# BeanShield.net
KiCad netlist of a schematic drawn in EAGLE
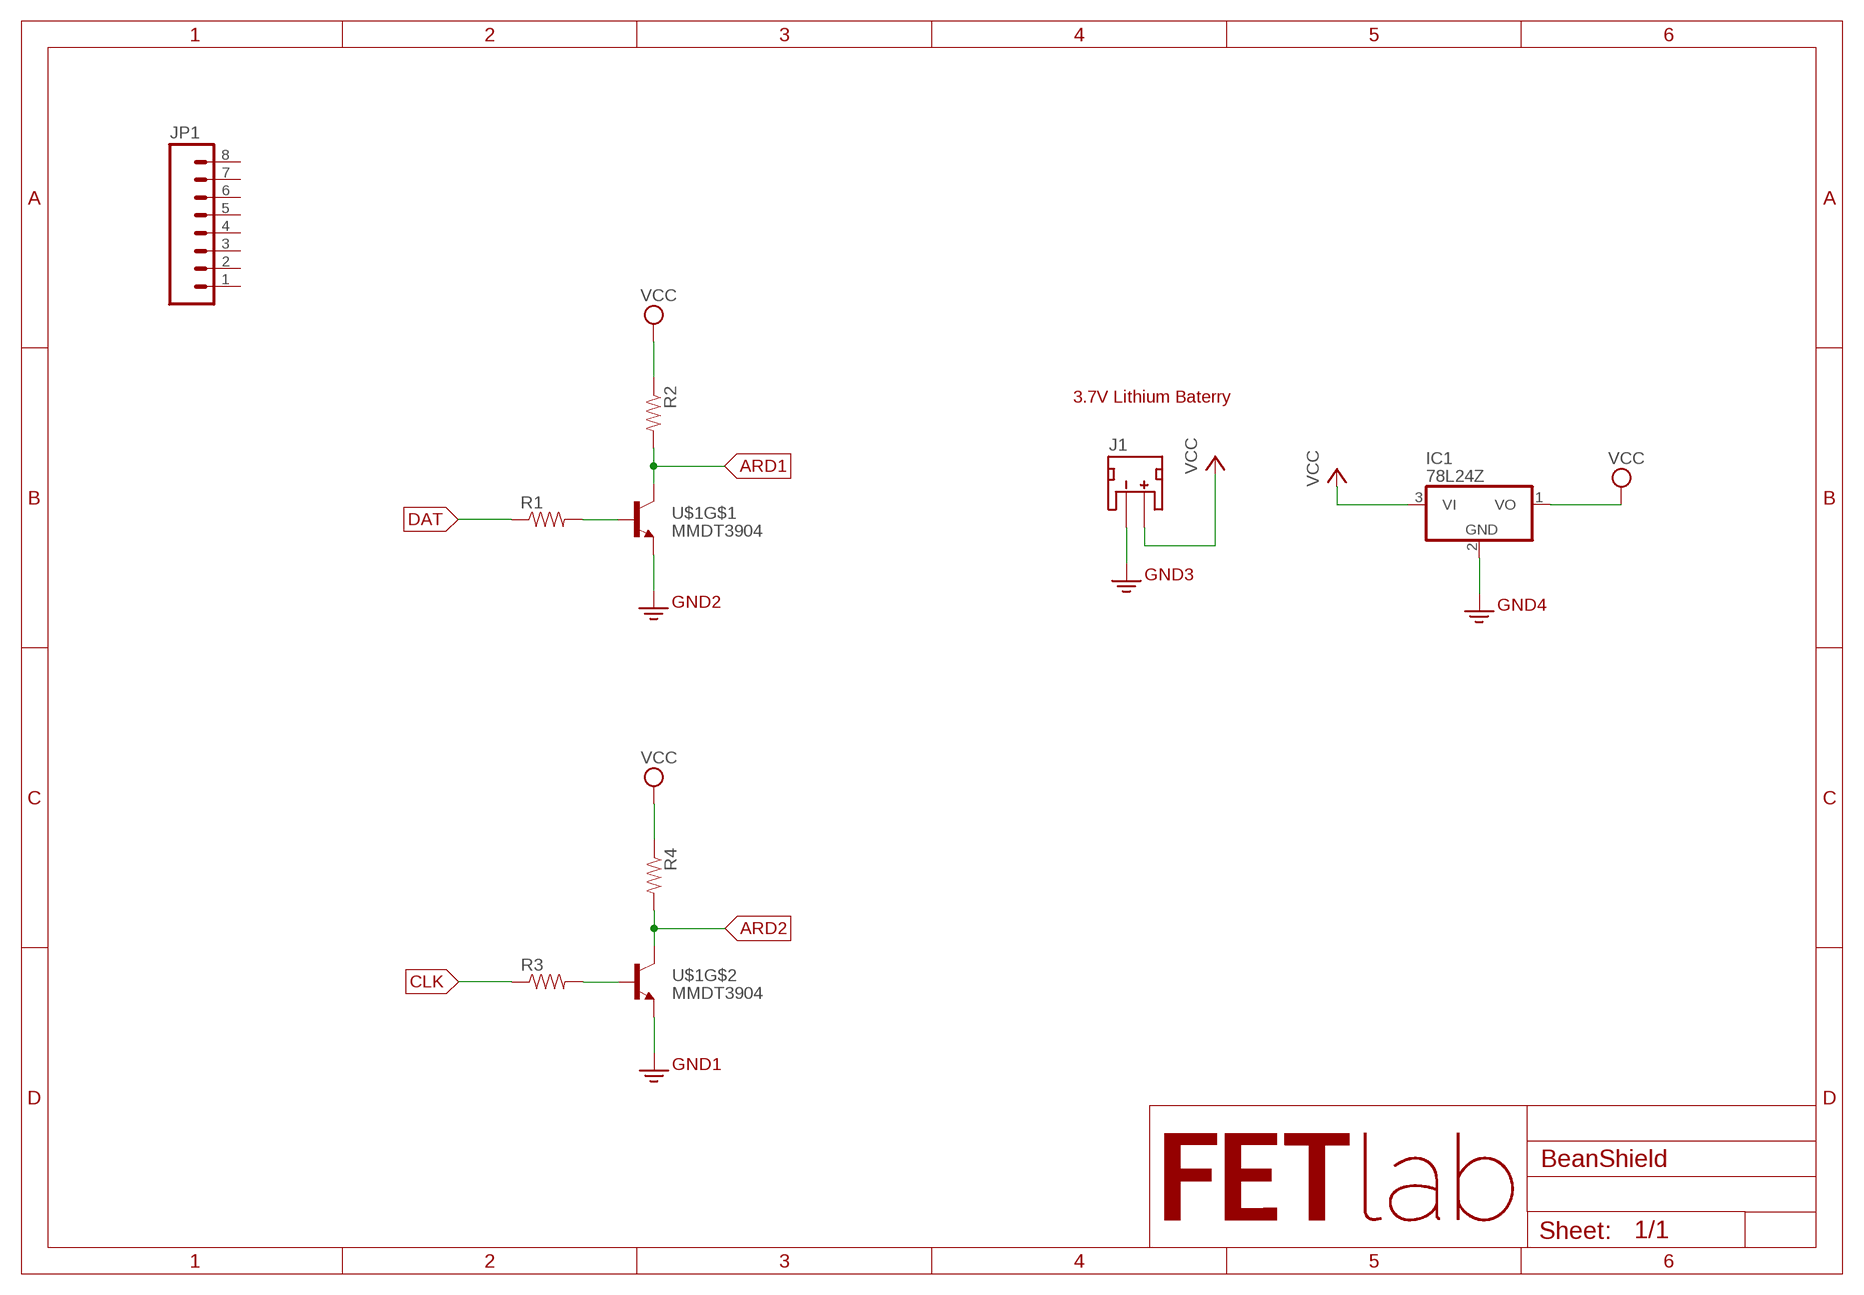
[diagram p0: schematic, sheet 1]

(export (version "E")
  (design (tool "Eeschema 10.0.6"))
  (components
    (comp (ref "IC1")
      (value "78L24Z")
      (footprint "eagle-import:TO92")
      (libsource (lib "eagle-import") (part "78ZL24"))
    )
    (comp (ref "J1")
      (value "JST_2MM_MALE")
      (footprint "eagle-import:JST-2-SMD")
      (libsource (lib "eagle-import") (part "JST_2MM_MALE"))
    )
    (comp (ref "JP1")
      (value "M08")
      (footprint "eagle-import:1X08_ROUND")
      (libsource (lib "eagle-import") (part "M08"))
    )
    (comp (ref "R1")
      (value "RESISTOR0402")
      (footprint "eagle-import:0402-RES")
      (libsource (lib "eagle-import") (part "RESISTOR0402"))
    )
    (comp (ref "R2")
      (value "RESISTOR0402")
      (footprint "eagle-import:0402-RES")
      (libsource (lib "eagle-import") (part "RESISTOR0402"))
    )
    (comp (ref "R3")
      (value "RESISTOR0402")
      (footprint "eagle-import:0402-RES")
      (libsource (lib "eagle-import") (part "RESISTOR0402"))
    )
    (comp (ref "R4")
      (value "RESISTOR0402")
      (footprint "eagle-import:0402-RES")
      (libsource (lib "eagle-import") (part "RESISTOR0402"))
    )
    (comp (ref "U$1")
      (value "MMDT3904")
      (footprint "eagle-import:SOT363")
      (libsource (lib "eagle-import") (part "TRANSISTOR_NPN2UPMMDT3904"))
    )
  )
  (nets
    (net (code "1") (name "ARD1") (class "Default")
      (node (ref "R2") (pin "2") (pinfunction "2_2") (pintype "passive"))
      (node (ref "U$1") (pin "6") (pinfunction "C_6") (pintype "passive"))
    )
    (net (code "2") (name "ARD2") (class "Default")
      (node (ref "R4") (pin "2") (pinfunction "2_2") (pintype "passive"))
      (node (ref "U$1") (pin "3") (pinfunction "C_3") (pintype "passive"))
    )
    (net (code "3") (name "CLK") (class "Default")
      (node (ref "R3") (pin "1") (pinfunction "1_1") (pintype "passive"))
    )
    (net (code "4") (name "DAT") (class "Default")
      (node (ref "R1") (pin "1") (pinfunction "1_1") (pintype "passive"))
    )
    (net (code "5") (name "GND2") (class "Default")
      (node (ref "IC1") (pin "2") (pinfunction "GND_2") (pintype "passive"))
      (node (ref "J1") (pin "1") (pinfunction "-_1") (pintype "bidirectional"))
      (node (ref "U$1") (pin "1") (pinfunction "E_1") (pintype "passive"))
      (node (ref "U$1") (pin "4") (pinfunction "E_4") (pintype "passive"))
    )
    (net (code "6") (name "Net-(U$1A-B)") (class "Default")
      (node (ref "R1") (pin "2") (pinfunction "2_2") (pintype "passive"))
      (node (ref "U$1") (pin "2") (pinfunction "B_2") (pintype "passive"))
    )
    (net (code "7") (name "Net-(U$1B-B)") (class "Default")
      (node (ref "R3") (pin "2") (pinfunction "2_2") (pintype "passive"))
      (node (ref "U$1") (pin "5") (pinfunction "B_5") (pintype "passive"))
    )
    (net (code "8") (name "VCC") (class "Default")
      (node (ref "IC1") (pin "1") (pinfunction "VO_1") (pintype "passive"))
      (node (ref "IC1") (pin "3") (pinfunction "VI_3") (pintype "input"))
      (node (ref "J1") (pin "2") (pinfunction "+_2") (pintype "bidirectional"))
      (node (ref "R2") (pin "1") (pinfunction "1_1") (pintype "passive"))
      (node (ref "R4") (pin "1") (pinfunction "1_1") (pintype "passive"))
    )
    (net (code "9") (name "unconnected-(J1-PAD1-PadNC1)") (class "Default")
      (node (ref "J1") (pin "NC1") (pinfunction "PAD1_NC1") (pintype "bidirectional"))
    )
    (net (code "10") (name "unconnected-(J1-PAD2-PadNC2)") (class "Default")
      (node (ref "J1") (pin "NC2") (pinfunction "PAD2_NC2") (pintype "bidirectional"))
    )
    (net (code "11") (name "unconnected-(JP1-Pad1)") (class "Default")
      (node (ref "JP1") (pin "1") (pinfunction "1_1") (pintype "passive"))
    )
    (net (code "12") (name "unconnected-(JP1-Pad2)") (class "Default")
      (node (ref "JP1") (pin "2") (pinfunction "2_2") (pintype "passive"))
    )
    (net (code "13") (name "unconnected-(JP1-Pad3)") (class "Default")
      (node (ref "JP1") (pin "3") (pinfunction "3_3") (pintype "passive"))
    )
    (net (code "14") (name "unconnected-(JP1-Pad4)") (class "Default")
      (node (ref "JP1") (pin "4") (pinfunction "4_4") (pintype "passive"))
    )
    (net (code "15") (name "unconnected-(JP1-Pad5)") (class "Default")
      (node (ref "JP1") (pin "5") (pinfunction "5_5") (pintype "passive"))
    )
    (net (code "16") (name "unconnected-(JP1-Pad6)") (class "Default")
      (node (ref "JP1") (pin "6") (pinfunction "6_6") (pintype "passive"))
    )
    (net (code "17") (name "unconnected-(JP1-Pad7)") (class "Default")
      (node (ref "JP1") (pin "7") (pinfunction "7_7") (pintype "passive"))
    )
    (net (code "18") (name "unconnected-(JP1-Pad8)") (class "Default")
      (node (ref "JP1") (pin "8") (pinfunction "8_8") (pintype "passive"))
    )
  )
)
